# meeting-meter-easyeda.net
KiCad netlist of a schematic drawn in EasyEDA
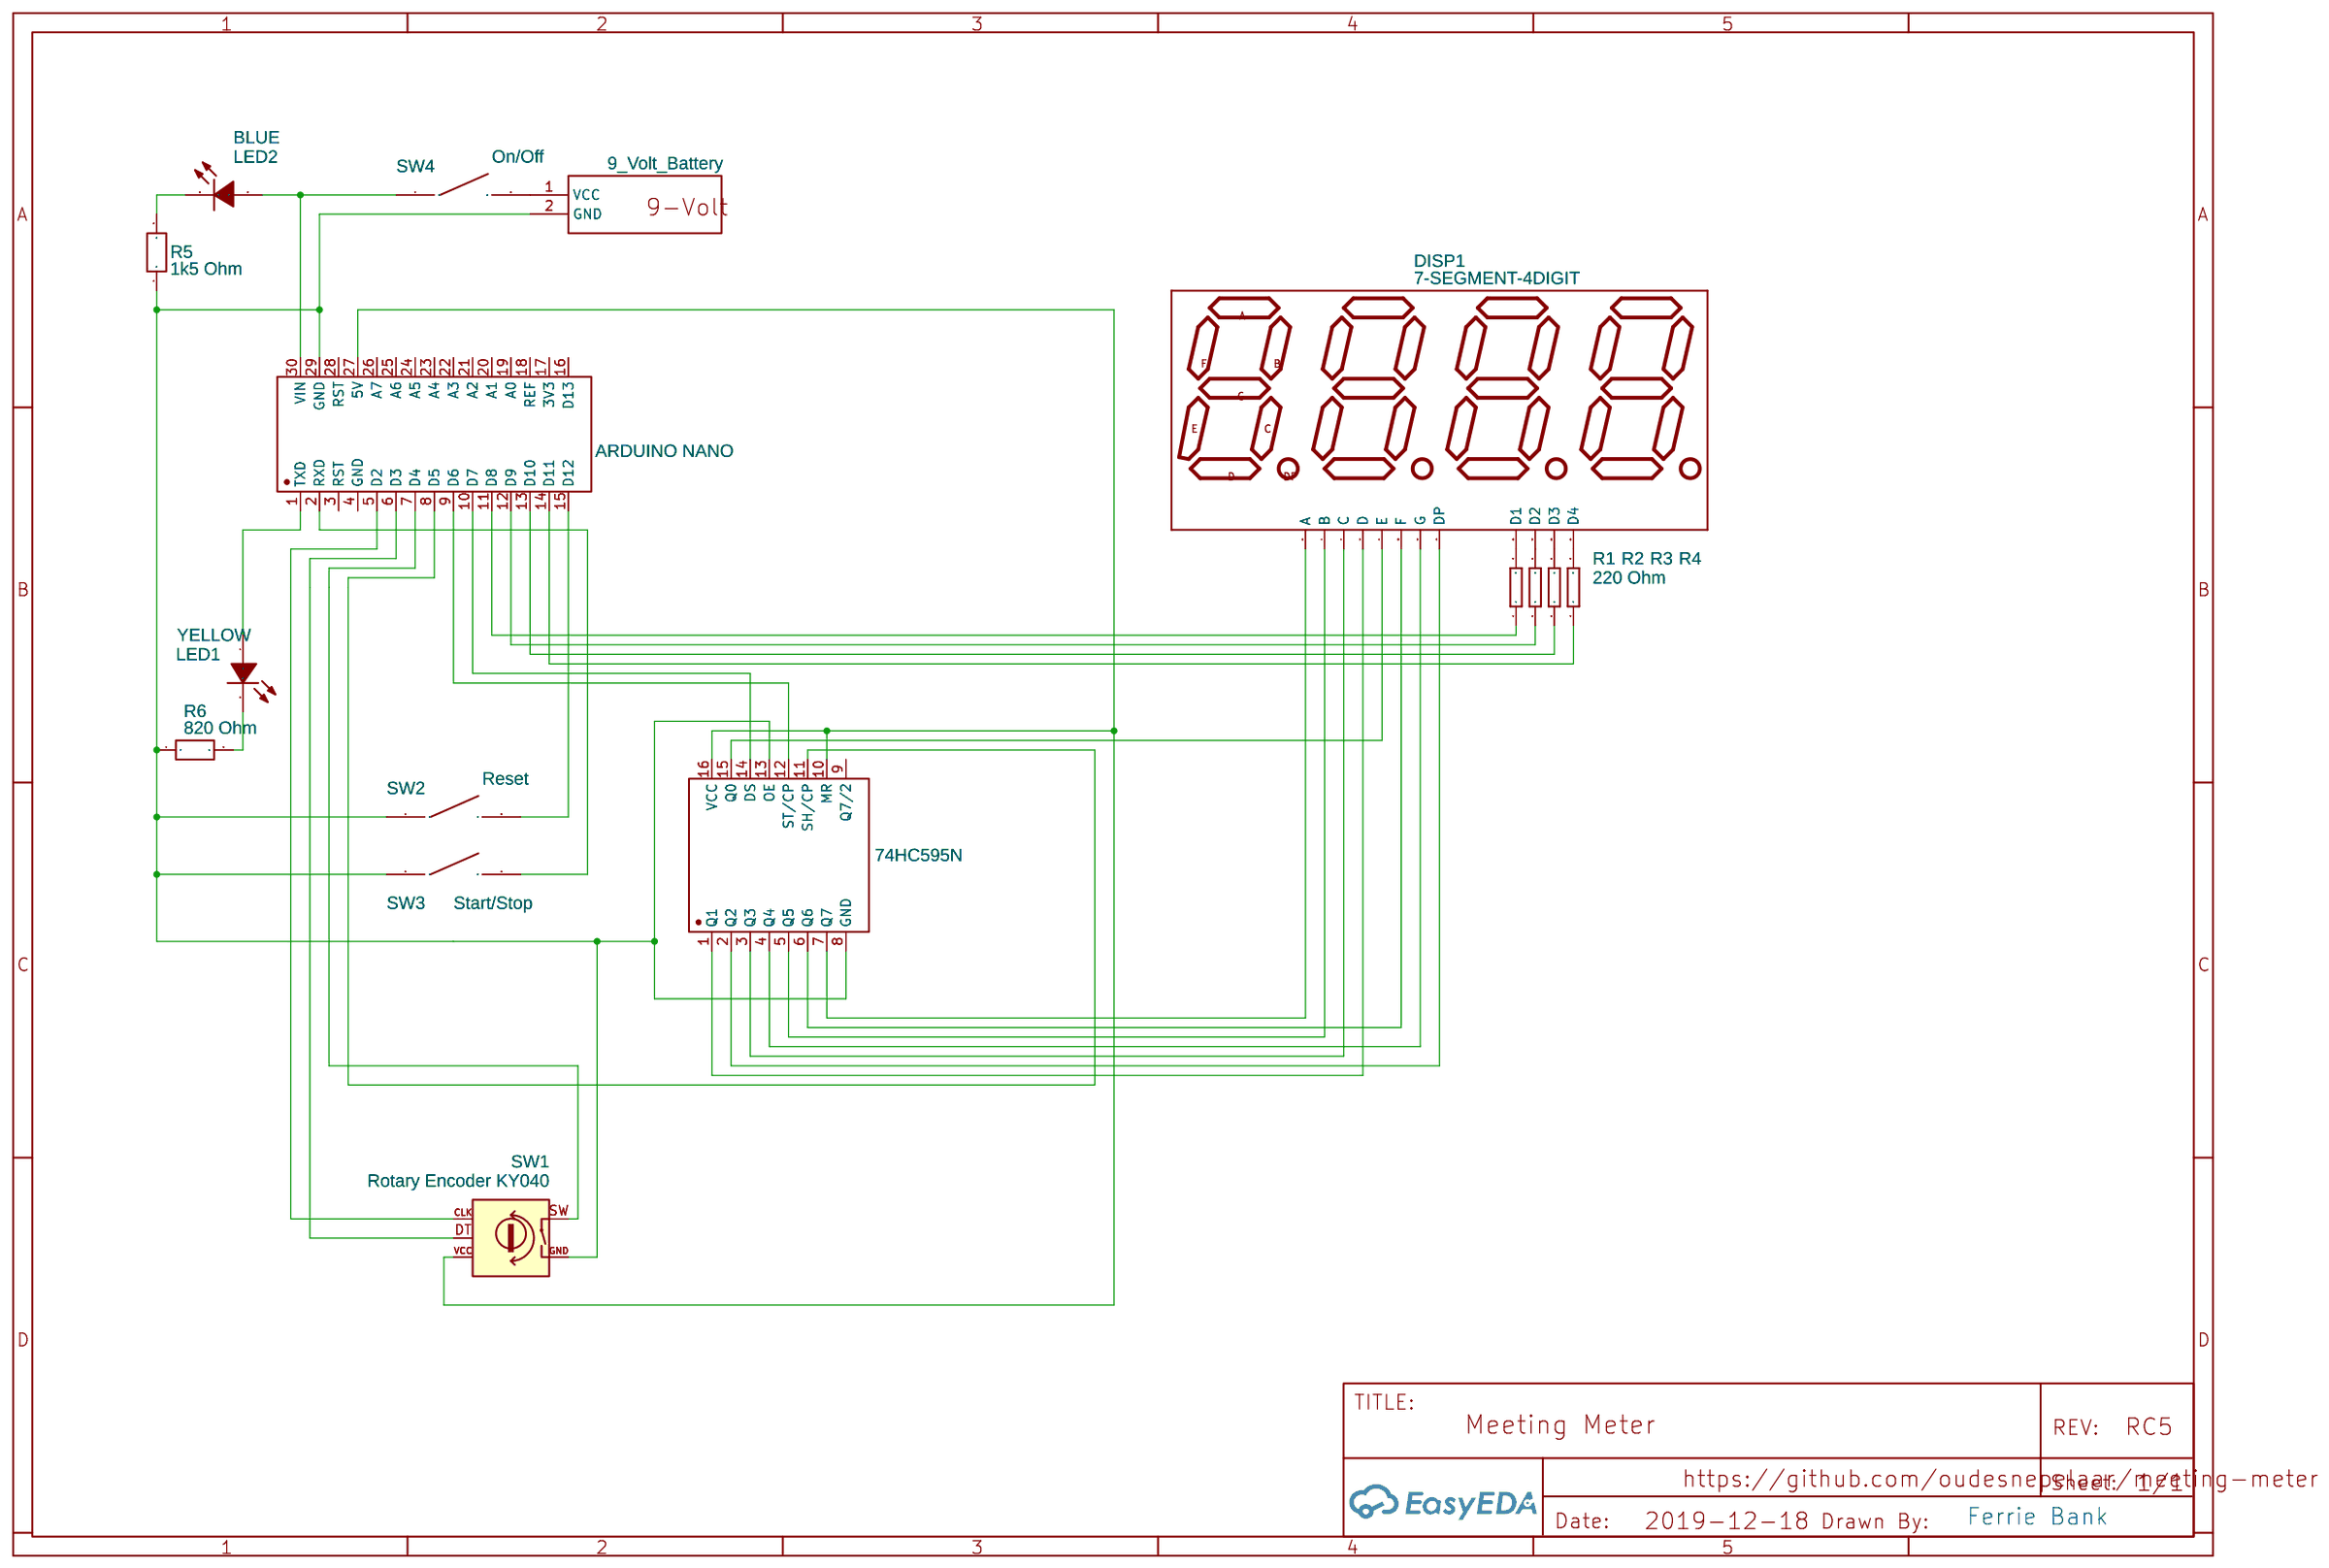
[diagram p0: schematic sheet]

(export (version "E")
  (design (tool "Eeschema 10.0.6"))
  (components
    (comp (ref "BT1")
      (value "9_Volt_Battery")
      (fields
        (field (name "BOM_Manufacturer Part") "No.7 battery3Section side by side battery box")
        (field (name "BOM_Supplier Part") "C9091")
      )
      (libsource (lib "") (part "Unknown_300_95"))
    )
    (comp (ref "DISP1") (value "7-SEGMENT-4DIGIT") (libsource (lib "") (part "Unknown_745_215")))
    (comp (ref "LED1")
      (value "YELLOW")
      (fields
        (field (name "BOM_Manufacturer Part") "204-10SURD/S530-A3")
        (field (name "BOM_Supplier Part") "C99772")
      )
      (libsource (lib "") (part "Unknown_125_345"))
    )
    (comp (ref "LED2")
      (value "BLUE")
      (fields
        (field (name "BOM_Manufacturer Part") "204-10SURD/S530-A3")
        (field (name "BOM_Supplier Part") "C99772")
      )
      (libsource (lib "") (part "Unknown_110_90"))
    )
    (comp (ref "R1") (value "220 Ohm") (libsource (lib "") (part "Unknown_785_300")))
    (comp (ref "R2") (value "RESISTOR") (libsource (lib "") (part "Unknown_795_300")))
    (comp (ref "R3") (value "RESISTOR") (libsource (lib "") (part "Unknown_805_300")))
    (comp (ref "R4") (value "RESISTOR") (libsource (lib "") (part "Unknown_815_300")))
    (comp (ref "R5") (value "1k5 Ohm") (libsource (lib "") (part "Res_AXIAL-0.3(1/8W)_EU_1")))
    (comp (ref "R6") (value "820 Ohm") (libsource (lib "") (part "Res_AXIAL-0.3(1/8W)_EU")))
    (comp (ref "SW1") (value "Rotary Encoder KY040") (libsource (lib "") (part "Unknown_260_640")))
    (comp (ref "SW2")
      (value "Reset")
      (fields (field (name "BOM_Manufacturer Part") "EVQ22705R") (field (name "BOM_Supplier Part") "C79156"))
      (libsource (lib "") (part "Unknown_230_420"))
    )
    (comp (ref "SW3")
      (value "Start/Stop")
      (fields (field (name "BOM_Manufacturer Part") "EVQ22705R") (field (name "BOM_Supplier Part") "C79156"))
      (libsource (lib "") (part "Unknown_230_450"))
    )
    (comp (ref "SW4")
      (value "On/Off")
      (fields (field (name "BOM_Manufacturer Part") "EVQ22705R") (field (name "BOM_Supplier Part") "C79156"))
      (libsource (lib "") (part "Unknown_235_95"))
    )
    (comp (ref "U1") (value "74HC595N") (libsource (lib "") (part "Unknown_400_440")))
    (comp (ref "U2")
      (value "ARDUINO NANO")
      (fields
        (field (name "BOM_Manufacturer Part") "NUCLEO-L432KC")
        (field (name "BOM_Supplier Part") "C94814")
      )
      (libsource (lib "") (part "Unknown_220_220"))
    )
  )
  (nets
    (net (code "1") (name "Net-(BT1-GND)") (class "Default")
      (node (ref "BT1") (pin "2") (pinfunction "GND_2") (pintype "unspecified"))
      (node (ref "R5") (pin "1") (pinfunction "1_1") (pintype "unspecified"))
      (node (ref "R6") (pin "1") (pinfunction "1_1") (pintype "unspecified"))
      (node (ref "SW1") (pin "GND") (pintype "input"))
      (node (ref "SW2") (pin "1") (pinfunction "1_1") (pintype "input"))
      (node (ref "SW3") (pin "1") (pinfunction "1_1") (pintype "input"))
      (node (ref "U1") (pin "13") (pinfunction "OE_13") (pintype "unspecified"))
      (node (ref "U1") (pin "8") (pinfunction "GND_8") (pintype "unspecified"))
      (node (ref "U2") (pin "29") (pinfunction "GND_29") (pintype "unspecified"))
    )
    (net (code "2") (name "Net-(BT1-VCC)") (class "Default")
      (node (ref "BT1") (pin "1") (pinfunction "VCC_1") (pintype "unspecified"))
      (node (ref "SW4") (pin "2") (pinfunction "2_2") (pintype "input"))
    )
    (net (code "3") (name "Net-(DISP1-A)") (class "Default")
      (node (ref "DISP1") (pin "11") (pinfunction "A_11") (pintype "unspecified"))
      (node (ref "U1") (pin "7") (pinfunction "Q7_7") (pintype "unspecified"))
    )
    (net (code "4") (name "Net-(DISP1-B)") (class "Default")
      (node (ref "DISP1") (pin "7") (pinfunction "B_7") (pintype "unspecified"))
      (node (ref "U1") (pin "5") (pinfunction "Q5_5") (pintype "unspecified"))
    )
    (net (code "5") (name "Net-(DISP1-C)") (class "Default")
      (node (ref "DISP1") (pin "4") (pinfunction "C_4") (pintype "unspecified"))
      (node (ref "U1") (pin "3") (pinfunction "Q3_3") (pintype "unspecified"))
    )
    (net (code "6") (name "Net-(DISP1-D)") (class "Default")
      (node (ref "DISP1") (pin "2") (pinfunction "D_2") (pintype "unspecified"))
      (node (ref "U1") (pin "1") (pinfunction "Q1_1") (pintype "unspecified"))
    )
    (net (code "7") (name "Net-(DISP1-D1)") (class "Default")
      (node (ref "DISP1") (pin "12") (pinfunction "D1_12") (pintype "unspecified"))
      (node (ref "R1") (pin "2") (pinfunction "2_2") (pintype "unspecified"))
    )
    (net (code "8") (name "Net-(DISP1-D2)") (class "Default")
      (node (ref "DISP1") (pin "9") (pinfunction "D2_9") (pintype "unspecified"))
      (node (ref "R2") (pin "2") (pinfunction "2_2") (pintype "unspecified"))
    )
    (net (code "9") (name "Net-(DISP1-D3)") (class "Default")
      (node (ref "DISP1") (pin "8") (pinfunction "D3_8") (pintype "unspecified"))
      (node (ref "R3") (pin "2") (pinfunction "2_2") (pintype "unspecified"))
    )
    (net (code "10") (name "Net-(DISP1-D4)") (class "Default")
      (node (ref "DISP1") (pin "6") (pinfunction "D4_6") (pintype "unspecified"))
      (node (ref "R4") (pin "2") (pinfunction "2_2") (pintype "unspecified"))
    )
    (net (code "11") (name "Net-(DISP1-DP)") (class "Default")
      (node (ref "DISP1") (pin "3") (pinfunction "DP_3") (pintype "unspecified"))
      (node (ref "U1") (pin "2") (pinfunction "Q2_2") (pintype "unspecified"))
    )
    (net (code "12") (name "Net-(DISP1-E)") (class "Default")
      (node (ref "DISP1") (pin "1") (pinfunction "E_1") (pintype "unspecified"))
      (node (ref "U1") (pin "15") (pinfunction "Q0_15") (pintype "unspecified"))
    )
    (net (code "13") (name "Net-(DISP1-F)") (class "Default")
      (node (ref "DISP1") (pin "10") (pinfunction "F_10") (pintype "unspecified"))
      (node (ref "U1") (pin "6") (pinfunction "Q6_6") (pintype "unspecified"))
    )
    (net (code "14") (name "Net-(DISP1-G)") (class "Default")
      (node (ref "DISP1") (pin "5") (pinfunction "G_5") (pintype "unspecified"))
      (node (ref "U1") (pin "4") (pinfunction "Q4_4") (pintype "unspecified"))
    )
    (net (code "15") (name "Net-(LED1-A)") (class "Default")
      (node (ref "LED1") (pin "1") (pinfunction "A_1") (pintype "unspecified"))
      (node (ref "U2") (pin "1") (pinfunction "TXD_1") (pintype "unspecified"))
    )
    (net (code "16") (name "Net-(LED1-K)") (class "Default")
      (node (ref "LED1") (pin "2") (pinfunction "K_2") (pintype "unspecified"))
      (node (ref "R6") (pin "2") (pinfunction "2_2") (pintype "unspecified"))
    )
    (net (code "17") (name "Net-(LED2-A)") (class "Default")
      (node (ref "LED2") (pin "1") (pinfunction "A_1") (pintype "unspecified"))
      (node (ref "SW4") (pin "1") (pinfunction "1_1") (pintype "input"))
      (node (ref "U2") (pin "30") (pinfunction "VIN_30") (pintype "unspecified"))
    )
    (net (code "18") (name "Net-(LED2-K)") (class "Default")
      (node (ref "LED2") (pin "2") (pinfunction "K_2") (pintype "unspecified"))
      (node (ref "R5") (pin "2") (pinfunction "2_2") (pintype "unspecified"))
    )
    (net (code "19") (name "Net-(U1-DS)") (class "Default")
      (node (ref "U1") (pin "14") (pinfunction "DS_14") (pintype "unspecified"))
      (node (ref "U2") (pin "10") (pinfunction "D7_10") (pintype "unspecified"))
    )
    (net (code "20") (name "Net-(U1-MR)") (class "Default")
      (node (ref "SW1") (pin "VCC") (pintype "input"))
      (node (ref "U1") (pin "10") (pinfunction "MR_10") (pintype "unspecified"))
      (node (ref "U1") (pin "16") (pinfunction "VCC_16") (pintype "unspecified"))
      (node (ref "U2") (pin "27") (pinfunction "5V_27") (pintype "unspecified"))
    )
    (net (code "21") (name "Net-(U1-SH{slash}CP)") (class "Default")
      (node (ref "U1") (pin "11") (pinfunction "SH/CP_11") (pintype "unspecified"))
      (node (ref "U2") (pin "8") (pinfunction "D5_8") (pintype "unspecified"))
    )
    (net (code "22") (name "Net-(U1-ST{slash}CP)") (class "Default")
      (node (ref "U1") (pin "12") (pinfunction "ST/CP_12") (pintype "unspecified"))
      (node (ref "U2") (pin "9") (pinfunction "D6_9") (pintype "unspecified"))
    )
    (net (code "23") (name "Net-(U2-D2)") (class "Default")
      (node (ref "SW1") (pin "CLK") (pintype "input"))
      (node (ref "U2") (pin "5") (pinfunction "D2_5") (pintype "unspecified"))
    )
    (net (code "24") (name "Net-(U2-D3)") (class "Default")
      (node (ref "SW1") (pin "DT") (pintype "input"))
      (node (ref "U2") (pin "6") (pinfunction "D3_6") (pintype "unspecified"))
    )
    (net (code "25") (name "Net-(U2-D4)") (class "Default")
      (node (ref "SW1") (pin "SW") (pintype "input"))
      (node (ref "U2") (pin "7") (pinfunction "D4_7") (pintype "unspecified"))
    )
    (net (code "26") (name "Net-(U2-D8)") (class "Default")
      (node (ref "R1") (pin "1") (pinfunction "1_1") (pintype "unspecified"))
      (node (ref "U2") (pin "11") (pinfunction "D8_11") (pintype "unspecified"))
    )
    (net (code "27") (name "Net-(U2-D9)") (class "Default")
      (node (ref "R2") (pin "1") (pinfunction "1_1") (pintype "unspecified"))
      (node (ref "U2") (pin "12") (pinfunction "D9_12") (pintype "unspecified"))
    )
    (net (code "28") (name "Net-(U2-D10)") (class "Default")
      (node (ref "R3") (pin "1") (pinfunction "1_1") (pintype "unspecified"))
      (node (ref "U2") (pin "13") (pinfunction "D10_13") (pintype "unspecified"))
    )
    (net (code "29") (name "Net-(U2-D11)") (class "Default")
      (node (ref "R4") (pin "1") (pinfunction "1_1") (pintype "unspecified"))
      (node (ref "U2") (pin "14") (pinfunction "D11_14") (pintype "unspecified"))
    )
    (net (code "30") (name "Net-(U2-D12)") (class "Default")
      (node (ref "SW2") (pin "2") (pinfunction "2_2") (pintype "input"))
      (node (ref "U2") (pin "15") (pinfunction "D12_15") (pintype "unspecified"))
    )
    (net (code "31") (name "Net-(U2-RXD)") (class "Default")
      (node (ref "SW3") (pin "2") (pinfunction "2_2") (pintype "input"))
      (node (ref "U2") (pin "2") (pinfunction "RXD_2") (pintype "unspecified"))
    )
    (net (code "32") (name "unconnected-(U1-Q7{slash}2-Pad9)") (class "Default")
      (node (ref "U1") (pin "9") (pinfunction "Q7/2_9") (pintype "unspecified"))
    )
    (net (code "33") (name "unconnected-(U2-3V3-Pad17)") (class "Default")
      (node (ref "U2") (pin "17") (pinfunction "3V3_17") (pintype "unspecified"))
    )
    (net (code "34") (name "unconnected-(U2-A0-Pad19)") (class "Default")
      (node (ref "U2") (pin "19") (pinfunction "A0_19") (pintype "unspecified"))
    )
    (net (code "35") (name "unconnected-(U2-A1-Pad20)") (class "Default")
      (node (ref "U2") (pin "20") (pinfunction "A1_20") (pintype "unspecified"))
    )
    (net (code "36") (name "unconnected-(U2-A2-Pad21)") (class "Default")
      (node (ref "U2") (pin "21") (pinfunction "A2_21") (pintype "unspecified"))
    )
    (net (code "37") (name "unconnected-(U2-A3-Pad22)") (class "Default")
      (node (ref "U2") (pin "22") (pinfunction "A3_22") (pintype "unspecified"))
    )
    (net (code "38") (name "unconnected-(U2-A4-Pad23)") (class "Default")
      (node (ref "U2") (pin "23") (pinfunction "A4_23") (pintype "unspecified"))
    )
    (net (code "39") (name "unconnected-(U2-A5-Pad24)") (class "Default")
      (node (ref "U2") (pin "24") (pinfunction "A5_24") (pintype "unspecified"))
    )
    (net (code "40") (name "unconnected-(U2-A6-Pad25)") (class "Default")
      (node (ref "U2") (pin "25") (pinfunction "A6_25") (pintype "unspecified"))
    )
    (net (code "41") (name "unconnected-(U2-A7-Pad26)") (class "Default")
      (node (ref "U2") (pin "26") (pinfunction "A7_26") (pintype "unspecified"))
    )
    (net (code "42") (name "unconnected-(U2-D13-Pad16)") (class "Default")
      (node (ref "U2") (pin "16") (pinfunction "D13_16") (pintype "unspecified"))
    )
    (net (code "43") (name "unconnected-(U2-GND-Pad4)") (class "Default")
      (node (ref "U2") (pin "4") (pinfunction "GND_4") (pintype "unspecified"))
    )
    (net (code "44") (name "unconnected-(U2-REF-Pad18)") (class "Default")
      (node (ref "U2") (pin "18") (pinfunction "REF_18") (pintype "unspecified"))
    )
    (net (code "45") (name "unconnected-(U2-RST-Pad3)") (class "Default")
      (node (ref "U2") (pin "3") (pinfunction "RST_3") (pintype "unspecified"))
    )
    (net (code "46") (name "unconnected-(U2-RST-Pad28)") (class "Default")
      (node (ref "U2") (pin "28") (pinfunction "RST_28") (pintype "unspecified"))
    )
  )
)
